# commUnit.net
KiCad netlist of a schematic drawn in EAGLE
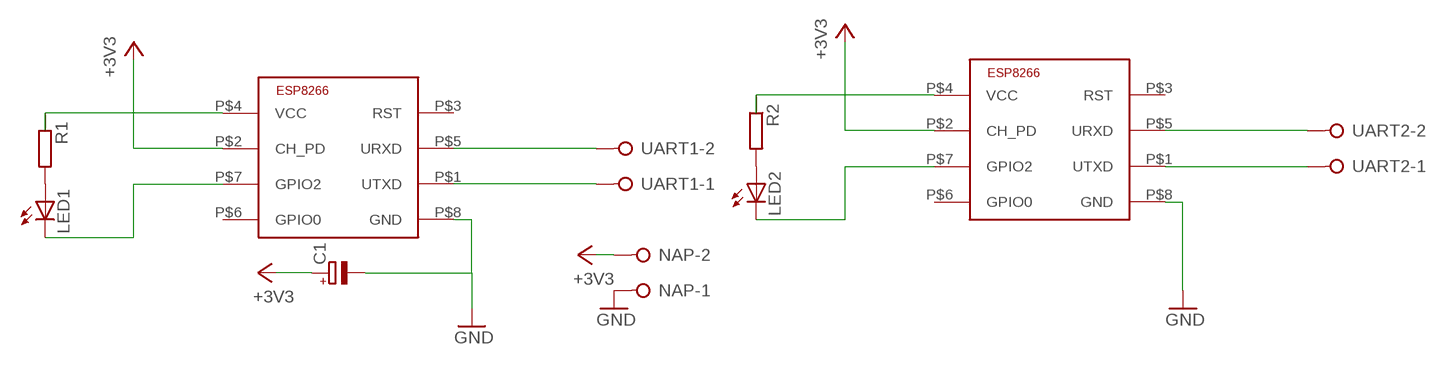
[diagram p0: schematic, sheet 1]

(export (version "E")
  (design (tool "Eeschema 10.0.6"))
  (components
    (comp (ref "C1")
      (value "CPOL-EUE3.5-10")
      (footprint "eagle-import:E3,5-10")
      (libsource (lib "eagle-import") (part "CPOL-EUE3.5-10"))
    )
    (comp (ref "LED1")
      (value "LED3MM")
      (footprint "eagle-import:LED3MM")
      (libsource (lib "eagle-import") (part "LED3MM"))
    )
    (comp (ref "LED2")
      (value "LED3MM")
      (footprint "eagle-import:LED3MM")
      (libsource (lib "eagle-import") (part "LED3MM"))
    )
    (comp (ref "NAP")
      (value "W237-02P")
      (footprint "eagle-import:W237-132")
      (libsource (lib "eagle-import") (part "W237-02P"))
    )
    (comp (ref "R1")
      (value "R-EU_0207/10")
      (footprint "eagle-import:0207_10")
      (libsource (lib "eagle-import") (part "R-EU_0207/10"))
    )
    (comp (ref "R2")
      (value "R-EU_0207/10")
      (footprint "eagle-import:0207_10")
      (libsource (lib "eagle-import") (part "R-EU_0207/10"))
    )
    (comp (ref "U$1")
      (value "ESP8266-01")
      (footprint "eagle-import:ESP-01")
      (libsource (lib "eagle-import") (part "ESP8266-01"))
    )
    (comp (ref "U$2")
      (value "ESP8266-01")
      (footprint "eagle-import:ESP-01")
      (libsource (lib "eagle-import") (part "ESP8266-01"))
    )
    (comp (ref "UART1")
      (value "W237-02P")
      (footprint "eagle-import:W237-132")
      (libsource (lib "eagle-import") (part "W237-02P"))
    )
    (comp (ref "UART2")
      (value "W237-02P")
      (footprint "eagle-import:W237-132")
      (libsource (lib "eagle-import") (part "W237-02P"))
    )
  )
  (nets
    (net (code "1") (name "+3V3") (class "Default")
      (node (ref "C1") (pin "+") (pinfunction "+_+") (pintype "passive"))
      (node (ref "NAP") (pin "2") (pinfunction "KL_2") (pintype "passive"))
      (node (ref "R1") (pin "1") (pinfunction "1_1") (pintype "passive"))
      (node (ref "R2") (pin "1") (pinfunction "1_1") (pintype "passive"))
      (node (ref "U$1") (pin "P$2") (pinfunction "CH_PD_P$2") (pintype "bidirectional"))
      (node (ref "U$1") (pin "P$4") (pinfunction "VCC_P$4") (pintype "bidirectional"))
      (node (ref "U$2") (pin "P$2") (pinfunction "CH_PD_P$2") (pintype "bidirectional"))
      (node (ref "U$2") (pin "P$4") (pinfunction "VCC_P$4") (pintype "bidirectional"))
    )
    (net (code "2") (name "GND") (class "Default")
      (node (ref "C1") (pin "-") (pinfunction "-_-") (pintype "passive"))
      (node (ref "NAP") (pin "1") (pinfunction "KL_1") (pintype "passive"))
      (node (ref "U$1") (pin "P$8") (pinfunction "GND_P$8") (pintype "bidirectional"))
      (node (ref "U$2") (pin "P$8") (pinfunction "GND_P$8") (pintype "bidirectional"))
    )
    (net (code "3") (name "Net-(LED1-C)") (class "Default")
      (node (ref "LED1") (pin "K") (pinfunction "C_K") (pintype "passive"))
      (node (ref "U$1") (pin "P$7") (pinfunction "GPIO2_P$7") (pintype "bidirectional"))
    )
    (net (code "4") (name "Net-(LED1-PadA)") (class "Default")
      (node (ref "LED1") (pin "A") (pinfunction "A_A") (pintype "passive"))
      (node (ref "R1") (pin "2") (pinfunction "2_2") (pintype "passive"))
    )
    (net (code "5") (name "Net-(LED2-C)") (class "Default")
      (node (ref "LED2") (pin "K") (pinfunction "C_K") (pintype "passive"))
      (node (ref "U$2") (pin "P$7") (pinfunction "GPIO2_P$7") (pintype "bidirectional"))
    )
    (net (code "6") (name "Net-(LED2-PadA)") (class "Default")
      (node (ref "LED2") (pin "A") (pinfunction "A_A") (pintype "passive"))
      (node (ref "R2") (pin "2") (pinfunction "2_2") (pintype "passive"))
    )
    (net (code "7") (name "Net-(U$1-URXD)") (class "Default")
      (node (ref "U$1") (pin "P$5") (pinfunction "URXD_P$5") (pintype "bidirectional"))
      (node (ref "UART1") (pin "2") (pinfunction "KL_2") (pintype "passive"))
    )
    (net (code "8") (name "Net-(U$1-UTXD)") (class "Default")
      (node (ref "U$1") (pin "P$1") (pinfunction "UTXD_P$1") (pintype "bidirectional"))
      (node (ref "UART1") (pin "1") (pinfunction "KL_1") (pintype "passive"))
    )
    (net (code "9") (name "Net-(U$2-URXD)") (class "Default")
      (node (ref "U$2") (pin "P$5") (pinfunction "URXD_P$5") (pintype "bidirectional"))
      (node (ref "UART2") (pin "2") (pinfunction "KL_2") (pintype "passive"))
    )
    (net (code "10") (name "Net-(U$2-UTXD)") (class "Default")
      (node (ref "U$2") (pin "P$1") (pinfunction "UTXD_P$1") (pintype "bidirectional"))
      (node (ref "UART2") (pin "1") (pinfunction "KL_1") (pintype "passive"))
    )
    (net (code "11") (name "unconnected-(U$1-GPIO0-PadP$6)") (class "Default")
      (node (ref "U$1") (pin "P$6") (pinfunction "GPIO0_P$6") (pintype "bidirectional"))
    )
    (net (code "12") (name "unconnected-(U$1-RST-PadP$3)") (class "Default")
      (node (ref "U$1") (pin "P$3") (pinfunction "RST_P$3") (pintype "bidirectional"))
    )
    (net (code "13") (name "unconnected-(U$2-GPIO0-PadP$6)") (class "Default")
      (node (ref "U$2") (pin "P$6") (pinfunction "GPIO0_P$6") (pintype "bidirectional"))
    )
    (net (code "14") (name "unconnected-(U$2-RST-PadP$3)") (class "Default")
      (node (ref "U$2") (pin "P$3") (pinfunction "RST_P$3") (pintype "bidirectional"))
    )
  )
)
